# Debug.net
KiCad netlist of a schematic drawn in Altium Designer
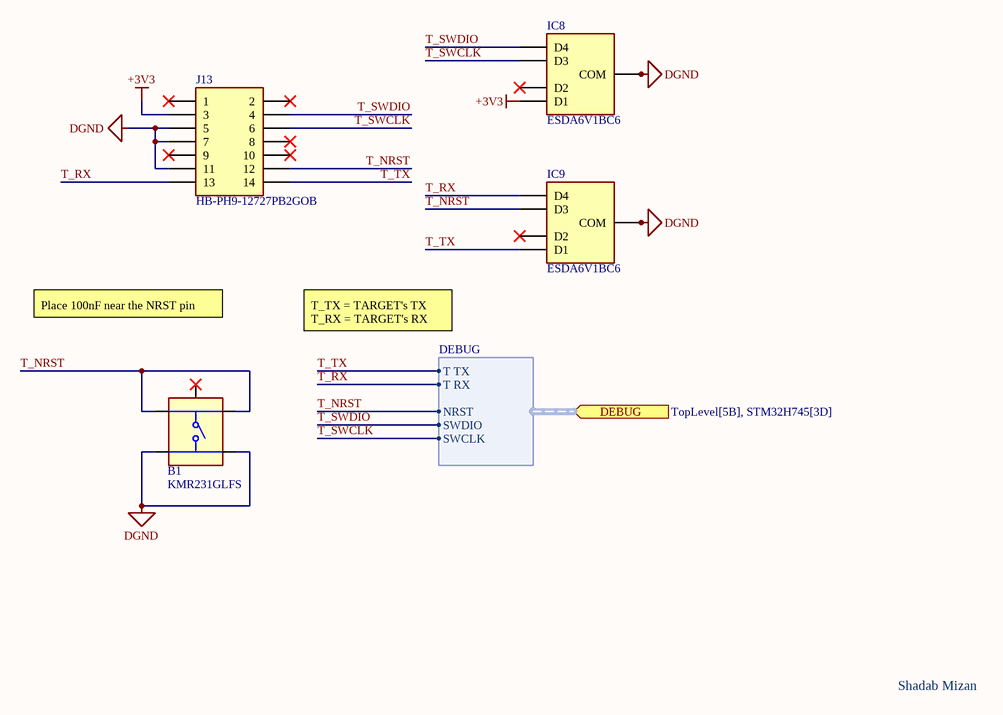
[diagram p0: Debug.SchDoc]

(export (version "E")
  (design (tool "Eeschema 10.0.6"))
  (components
    (comp (ref "B1")
      (value "KMR231GLFS")
      (footprint "KMR231GLFS")
      (description "Tactile Switch SPST 300gf 1.9mm Gull Wing 4.6mm x 2.8mm Surface Mount")
      (fields (field (name "LCSC PART #") "C99271"))
      (libsource (lib "flight-controller") (part "KMR231GLFS"))
    )
    (comp (ref "IC8")
      (value "ESDA6V1BC6")
      (footprint "SOT95P280X145-6N")
      (description "Clamp Ipp Tvs Diode Surface Mount SOT-23-6")
      (fields (field (name "LCSC PART #") "C495220"))
      (libsource (lib "flight-controller") (part "ESDA6V1BC6"))
    )
    (comp (ref "IC9")
      (value "ESDA6V1BC6")
      (footprint "SOT95P280X145-6N")
      (description "Clamp Ipp Tvs Diode Surface Mount SOT-23-6")
      (fields (field (name "LCSC PART #") "C495220"))
      (libsource (lib "flight-controller") (part "ESDA6V1BC6"))
    )
    (comp (ref "J13")
      (value "HB-PH9-12727PB2GOB")
      (footprint "HB-PH9-12727PB2GOB")
      (fields (field (name "LCSC PART #") "C6332251"))
      (libsource (lib "flight-controller") (part "HB-PH9-12727PB2GOB"))
    )
  )
  (nets
    (net (code "2") (name "+3V3") (class "Default")
      (node (ref "IC8") (pin "1") (pinfunction "D1_1") (pintype "passive"))
      (node (ref "J13") (pin "3") (pinfunction "3_3") (pintype "passive"))
    )
    (net (code "3") (name "/T_NRST") (class "Default")
      (node (ref "B1") (pin "1") (pinfunction "1_1") (pintype "passive"))
      (node (ref "B1") (pin "2") (pinfunction "2_2") (pintype "passive"))
      (node (ref "IC9") (pin "4") (pinfunction "D3_4") (pintype "passive"))
      (node (ref "J13") (pin "12") (pinfunction "12_12") (pintype "passive"))
    )
    (net (code "4") (name "/T_RX") (class "Default")
      (node (ref "IC9") (pin "6") (pinfunction "D4_6") (pintype "passive"))
      (node (ref "J13") (pin "13") (pinfunction "13_13") (pintype "passive"))
    )
    (net (code "5") (name "/T_SWCLK") (class "Default")
      (node (ref "IC8") (pin "4") (pinfunction "D3_4") (pintype "passive"))
      (node (ref "J13") (pin "6") (pinfunction "6_6") (pintype "passive"))
    )
    (net (code "6") (name "/T_SWDIO") (class "Default")
      (node (ref "IC8") (pin "6") (pinfunction "D4_6") (pintype "passive"))
      (node (ref "J13") (pin "4") (pinfunction "4_4") (pintype "passive"))
    )
    (net (code "7") (name "/T_TX") (class "Default")
      (node (ref "IC9") (pin "1") (pinfunction "D1_1") (pintype "passive"))
      (node (ref "J13") (pin "14") (pinfunction "14_14") (pintype "passive"))
    )
    (net (code "9") (name "DGND") (class "Default")
      (node (ref "B1") (pin "3") (pinfunction "3_3") (pintype "passive"))
      (node (ref "B1") (pin "4") (pinfunction "4_4") (pintype "passive"))
      (node (ref "IC8") (pin "2") (pinfunction "COM_2") (pintype "passive"))
      (node (ref "IC8") (pin "5") (pinfunction "COM_5") (pintype "passive"))
      (node (ref "IC9") (pin "2") (pinfunction "COM_2") (pintype "passive"))
      (node (ref "IC9") (pin "5") (pinfunction "COM_5") (pintype "passive"))
      (node (ref "J13") (pin "11") (pinfunction "11_11") (pintype "passive"))
      (node (ref "J13") (pin "5") (pinfunction "5_5") (pintype "passive"))
      (node (ref "J13") (pin "7") (pinfunction "7_7") (pintype "passive"))
    )
    (net (code "10") (name "unconnected-(B1-Pad5)") (class "Default")
      (node (ref "B1") (pin "5") (pinfunction "5_5") (pintype "passive+no_connect"))
    )
    (net (code "11") (name "unconnected-(IC8-D2-Pad3)") (class "Default")
      (node (ref "IC8") (pin "3") (pinfunction "D2_3") (pintype "passive+no_connect"))
    )
    (net (code "12") (name "unconnected-(IC9-D2-Pad3)") (class "Default")
      (node (ref "IC9") (pin "3") (pinfunction "D2_3") (pintype "passive+no_connect"))
    )
    (net (code "13") (name "unconnected-(J13-Pad1)") (class "Default")
      (node (ref "J13") (pin "1") (pinfunction "1_1") (pintype "passive+no_connect"))
    )
    (net (code "14") (name "unconnected-(J13-Pad2)") (class "Default")
      (node (ref "J13") (pin "2") (pinfunction "2_2") (pintype "passive+no_connect"))
    )
    (net (code "15") (name "unconnected-(J13-Pad8)") (class "Default")
      (node (ref "J13") (pin "8") (pinfunction "8_8") (pintype "passive+no_connect"))
    )
    (net (code "16") (name "unconnected-(J13-Pad9)") (class "Default")
      (node (ref "J13") (pin "9") (pinfunction "9_9") (pintype "passive+no_connect"))
    )
    (net (code "17") (name "unconnected-(J13-Pad10)") (class "Default")
      (node (ref "J13") (pin "10") (pinfunction "10_10") (pintype "passive+no_connect"))
    )
  )
)
